# NRF_Transciever.net
KiCad netlist of a schematic drawn in Altium Designer
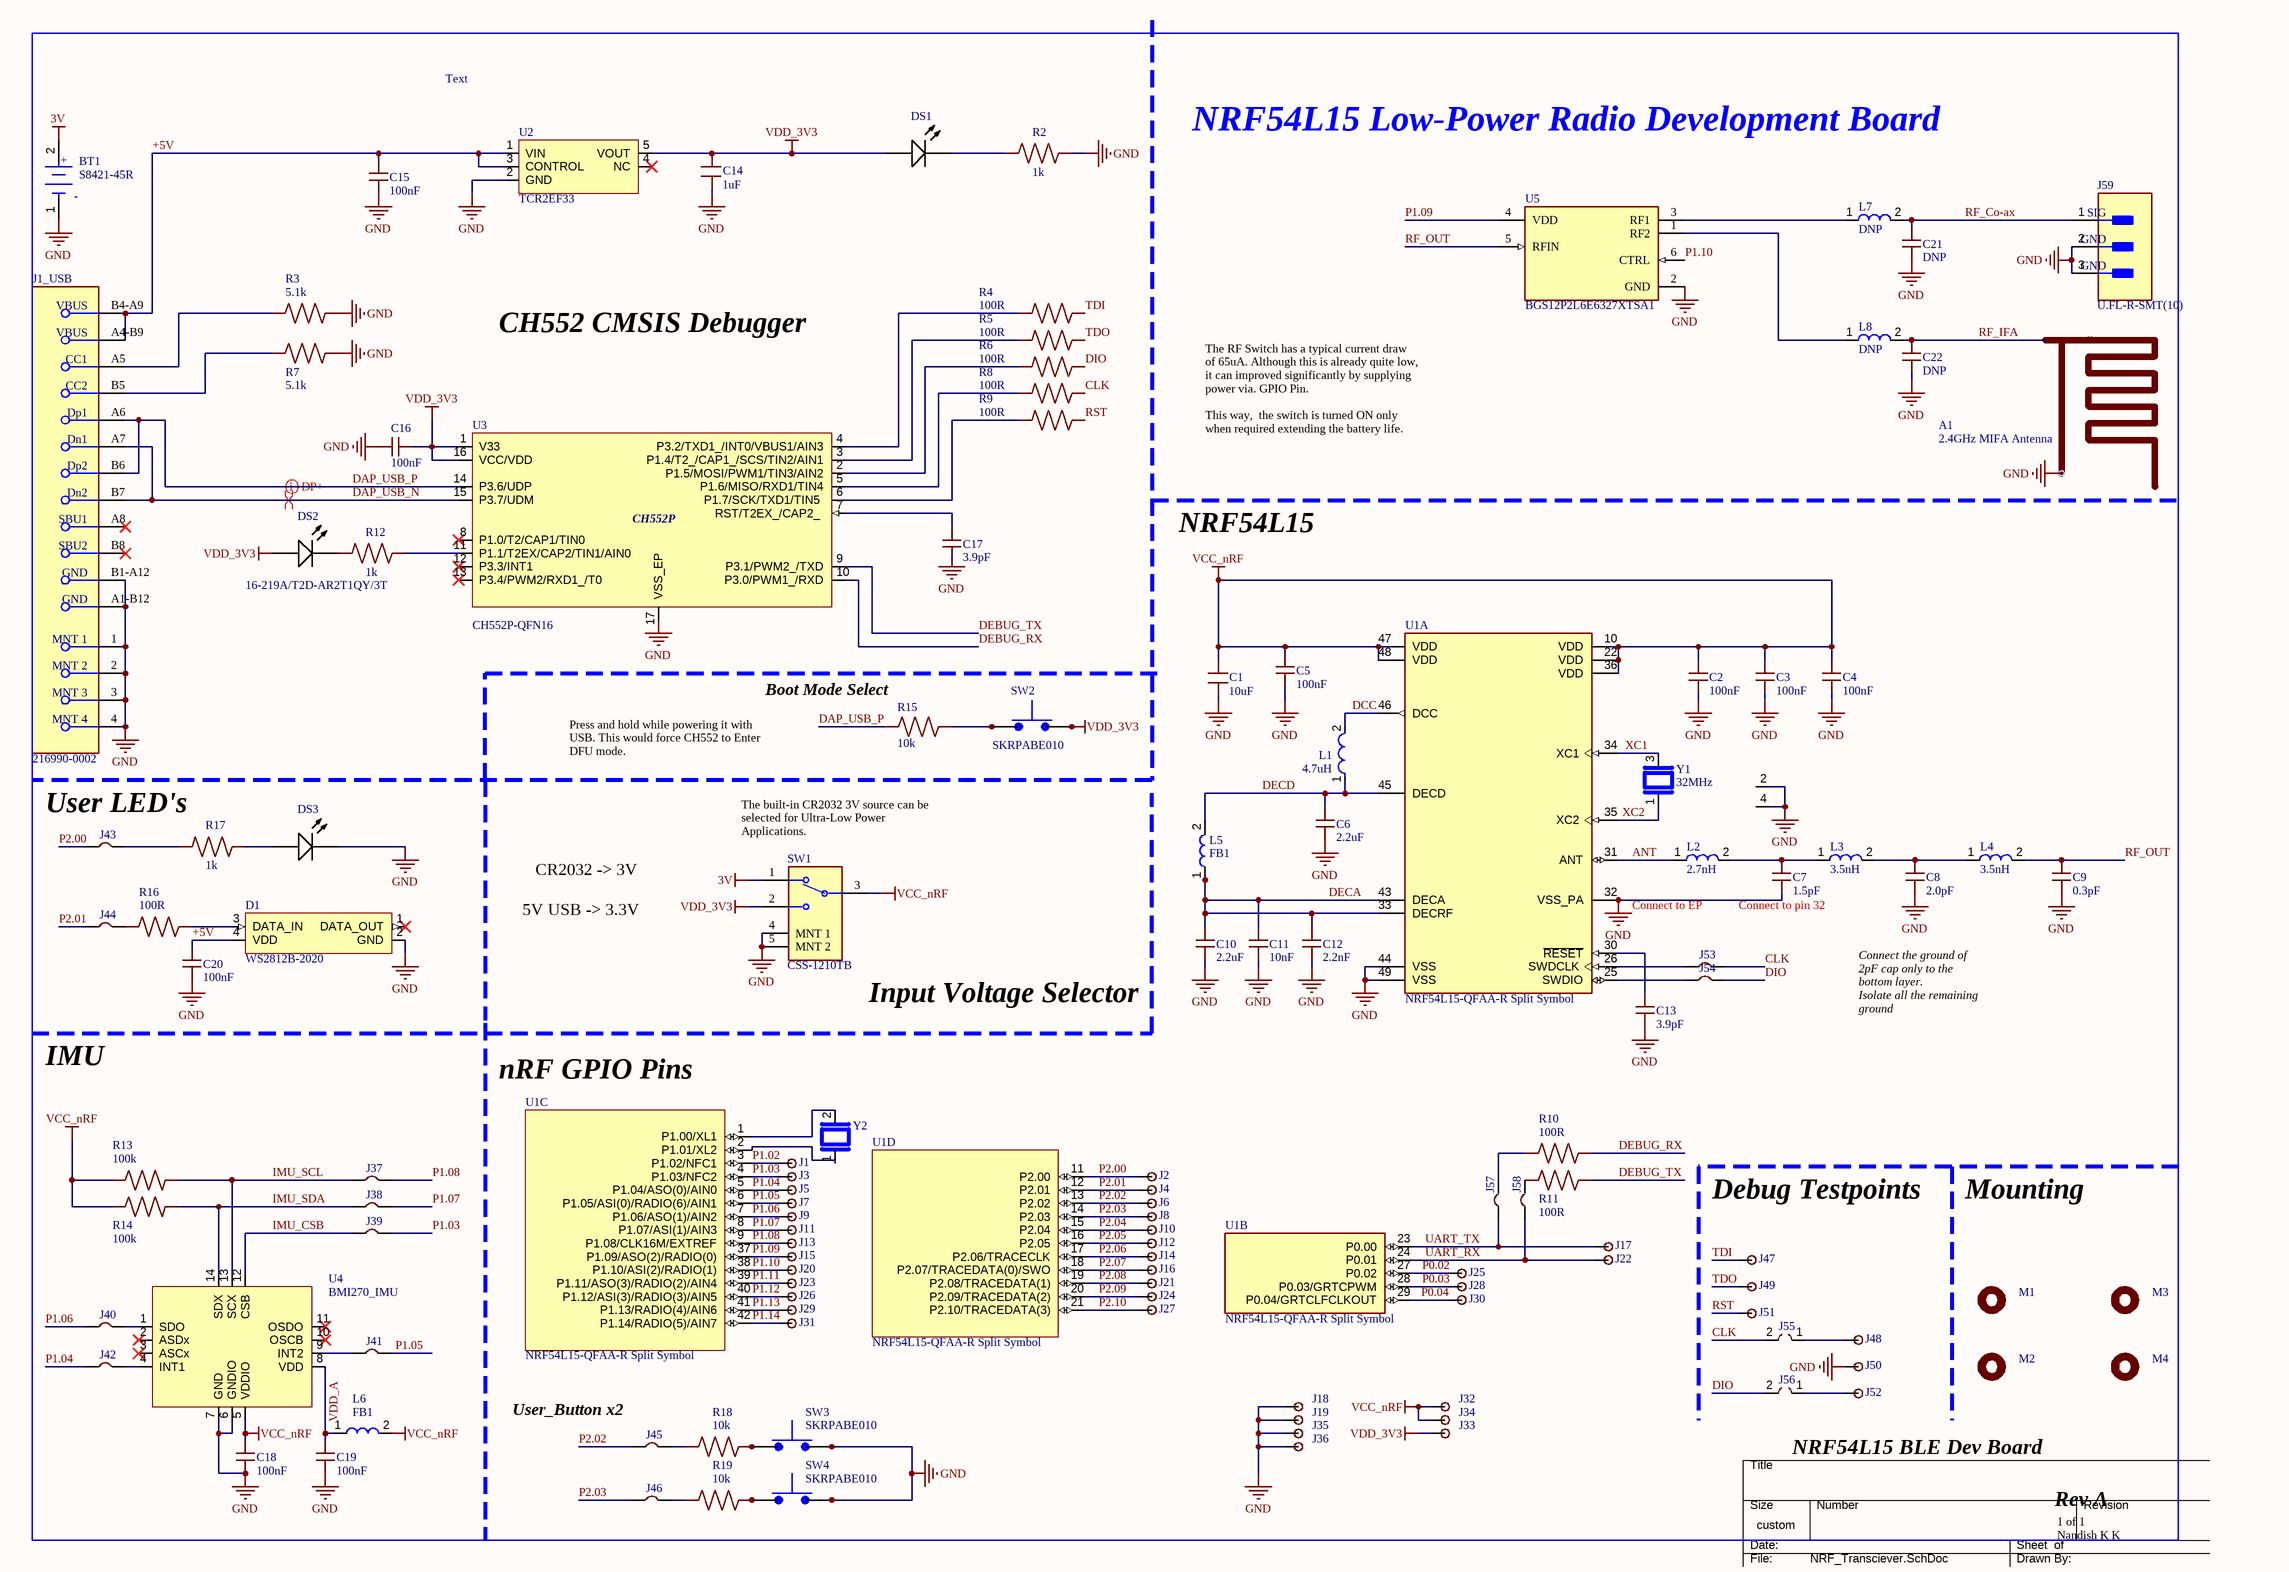
[diagram p0: NRF_Transciever.SchDoc]

(export (version "E")
  (design (tool "Eeschema 10.0.6"))
  (components
    (comp (ref "A1")
      (value "2.4GHz MIFA Antenna")
      (footprint "2.4GHz MIFA")
      (description "2.4GHz Meandered Inverted F Antenna from Cypress appnote AN91445")
      (libsource (lib "Generic_Schematic_Library") (part "2.4GHz MIFA"))
    )
    (comp (ref "BT1")
      (value "S8421-45R")
      (footprint "FP-S8421-45R-MFG")
      (description "BATTERY HOLDER COIN 20MM SMD")
      (libsource (lib "Altium Content Vault") (part "60d3b5b901a8747834971d0eb8cf3fd"))
    )
    (comp (ref "C1")
      (value "10uF")
      (footprint "0402_SMD_CAPACITOR")
      (description "Capacitor SMD 0402 Generic")
      (libsource (lib "Generic_Schematic_Library") (part "CAP_0402"))
    )
    (comp (ref "C2")
      (value "100nF")
      (footprint "0201 SMD Capacitor")
      (description "Capacitor SMD 0201 Generic")
      (libsource (lib "Generic_Schematic_Library") (part "CAP_0201"))
    )
    (comp (ref "C3")
      (value "100nF")
      (footprint "0201 SMD Capacitor")
      (description "Capacitor SMD 0201 Generic")
      (libsource (lib "Generic_Schematic_Library") (part "CAP_0201"))
    )
    (comp (ref "C4")
      (value "100nF")
      (footprint "0201 SMD Capacitor")
      (description "Capacitor SMD 0201 Generic")
      (libsource (lib "Generic_Schematic_Library") (part "CAP_0201"))
    )
    (comp (ref "C5")
      (value "100nF")
      (footprint "0201 SMD Capacitor")
      (description "Capacitor SMD 0201 Generic")
      (libsource (lib "Generic_Schematic_Library") (part "CAP_0201"))
    )
    (comp (ref "C6")
      (value "2.2uF")
      (footprint "0201 SMD Capacitor")
      (description "Capacitor SMD 0201 Generic")
      (libsource (lib "Generic_Schematic_Library") (part "CAP_0201"))
    )
    (comp (ref "C7")
      (value "1.5pF")
      (footprint "0201 SMD Capacitor")
      (description "Capacitor SMD 0201 Generic")
      (libsource (lib "Generic_Schematic_Library") (part "CAP_0201"))
    )
    (comp (ref "C8")
      (value "2.0pF")
      (footprint "0201 SMD Capacitor")
      (description "Capacitor SMD 0201 Generic")
      (libsource (lib "Generic_Schematic_Library") (part "CAP_0201"))
    )
    (comp (ref "C9")
      (value "0.3pF")
      (footprint "0201 SMD Capacitor")
      (description "Capacitor SMD 0201 Generic")
      (libsource (lib "Generic_Schematic_Library") (part "CAP_0201"))
    )
    (comp (ref "C10")
      (value "2.2uF")
      (footprint "0201 SMD Capacitor")
      (description "Capacitor SMD 0201 Generic")
      (libsource (lib "Generic_Schematic_Library") (part "CAP_0201"))
    )
    (comp (ref "C11")
      (value "10nF")
      (footprint "0201 SMD Capacitor")
      (description "Capacitor SMD 0201 Generic")
      (libsource (lib "Generic_Schematic_Library") (part "CAP_0201"))
    )
    (comp (ref "C12")
      (value "2.2nF")
      (footprint "0201 SMD Capacitor")
      (description "Capacitor SMD 0201 Generic")
      (libsource (lib "Generic_Schematic_Library") (part "CAP_0201"))
    )
    (comp (ref "C13")
      (value "3.9pF")
      (footprint "0201 SMD Capacitor")
      (description "Capacitor SMD 0201 Generic")
      (libsource (lib "Generic_Schematic_Library") (part "CAP_0201"))
    )
    (comp (ref "C14")
      (value "1uF")
      (footprint "0402_SMD_CAPACITOR")
      (description "Capacitor SMD 0402 Generic")
      (libsource (lib "Generic_Schematic_Library") (part "CAP_0402"))
    )
    (comp (ref "C15")
      (value "100nF")
      (footprint "0201 SMD Capacitor")
      (description "Capacitor SMD 0201 Generic")
      (libsource (lib "Generic_Schematic_Library") (part "CAP_0201"))
    )
    (comp (ref "C16")
      (value "100nF")
      (footprint "0201 SMD Capacitor")
      (description "Capacitor SMD 0201 Generic")
      (libsource (lib "Generic_Schematic_Library") (part "CAP_0201"))
    )
    (comp (ref "C17")
      (value "3.9pF")
      (footprint "0201 SMD Capacitor")
      (description "Capacitor SMD 0201 Generic")
      (libsource (lib "Generic_Schematic_Library") (part "CAP_0201"))
    )
    (comp (ref "C18")
      (value "100nF")
      (footprint "0201 SMD Capacitor")
      (description "Capacitor SMD 0201 Generic")
      (libsource (lib "Generic_Schematic_Library") (part "CAP_0201"))
    )
    (comp (ref "C19")
      (value "100nF")
      (footprint "0201 SMD Capacitor")
      (description "Capacitor SMD 0201 Generic")
      (libsource (lib "Generic_Schematic_Library") (part "CAP_0201"))
    )
    (comp (ref "C20")
      (value "100nF")
      (footprint "0201 SMD Capacitor")
      (description "Capacitor SMD 0201 Generic")
      (libsource (lib "Generic_Schematic_Library") (part "CAP_0201"))
    )
    (comp (ref "C21")
      (value "DNP")
      (footprint "0201 SMD Capacitor")
      (description "Capacitor SMD 0201 Generic")
      (libsource (lib "Generic_Schematic_Library") (part "CAP_0201"))
    )
    (comp (ref "C22")
      (value "DNP")
      (footprint "0201 SMD Capacitor")
      (description "Capacitor SMD 0201 Generic")
      (libsource (lib "Generic_Schematic_Library") (part "CAP_0201"))
    )
    (comp (ref "D1")
      (value "WS2812B-2020")
      (footprint "ws2812b-2020")
      (description "RGB LED (Built-in IC) 2x2mm SMD")
      (libsource (lib "Generic_Schematic_Library") (part "WS2812B-2020"))
    )
    (comp (ref "DS1")
      (value "16-219A/T2D-AR2T1QY/3T")
      (footprint "EVRL-0402-2_V")
      (description "Chip LED, White, 5 V, 10 mA, 30 mW, -40 to 85 degC, 2-Pin SMD (0402), RoHS, Tape and Reel")
      (fields (field (name "POWER") "30mW") (field (name "MANUFACTURER") "Everlight Electronics"))
      (libsource (lib "nandish kk") (part "LED-WHITE-AK-2"))
    )
    (comp (ref "DS2")
      (value "16-219A/T2D-AR2T1QY/3T")
      (footprint "EVRL-0402-2_V")
      (description "Chip LED, White, 5 V, 10 mA, 30 mW, -40 to 85 degC, 2-Pin SMD (0402), RoHS, Tape and Reel")
      (fields (field (name "POWER") "30mW") (field (name "MANUFACTURER") "Everlight Electronics"))
      (libsource (lib "nandish kk") (part "LED-WHITE-AK-2"))
    )
    (comp (ref "DS3")
      (value "16-219A/T2D-AR2T1QY/3T")
      (footprint "EVRL-0402-2_V")
      (description "Chip LED, White, 5 V, 10 mA, 30 mW, -40 to 85 degC, 2-Pin SMD (0402), RoHS, Tape and Reel")
      (fields (field (name "POWER") "30mW") (field (name "MANUFACTURER") "Everlight Electronics"))
      (libsource (lib "nandish kk") (part "LED-WHITE-AK-2"))
    )
    (comp (ref "J1")
      (value "Single_Header_2.54mm")
      (footprint "Single_Header_2.54mm")
      (libsource (lib "Generic_Schematic_Library") (part "Single_Header_2.54mm"))
    )
    (comp (ref "J1_USB")
      (value "216990-0002")
      (footprint "FP-216990-0002-MFG")
      (description "CONN RCP USB2.0 TYP C 24P SMD RA")
      (libsource (lib "Altium Content Vault") (part "7e081d3bdd84dd7df1daf8a7a06d5b3"))
    )
    (comp (ref "J2")
      (value "Single_Header_2.54mm")
      (footprint "Single_Header_2.54mm")
      (libsource (lib "Generic_Schematic_Library") (part "Single_Header_2.54mm"))
    )
    (comp (ref "J3")
      (value "Single_Header_2.54mm")
      (footprint "Single_Header_2.54mm")
      (libsource (lib "Generic_Schematic_Library") (part "Single_Header_2.54mm"))
    )
    (comp (ref "J4")
      (value "Single_Header_2.54mm")
      (footprint "Single_Header_2.54mm")
      (libsource (lib "Generic_Schematic_Library") (part "Single_Header_2.54mm"))
    )
    (comp (ref "J5")
      (value "Single_Header_2.54mm")
      (footprint "Single_Header_2.54mm")
      (libsource (lib "Generic_Schematic_Library") (part "Single_Header_2.54mm"))
    )
    (comp (ref "J6")
      (value "Single_Header_2.54mm")
      (footprint "Single_Header_2.54mm")
      (libsource (lib "Generic_Schematic_Library") (part "Single_Header_2.54mm"))
    )
    (comp (ref "J7")
      (value "Single_Header_2.54mm")
      (footprint "Single_Header_2.54mm")
      (libsource (lib "Generic_Schematic_Library") (part "Single_Header_2.54mm"))
    )
    (comp (ref "J8")
      (value "Single_Header_2.54mm")
      (footprint "Single_Header_2.54mm")
      (libsource (lib "Generic_Schematic_Library") (part "Single_Header_2.54mm"))
    )
    (comp (ref "J9")
      (value "Single_Header_2.54mm")
      (footprint "Single_Header_2.54mm")
      (libsource (lib "Generic_Schematic_Library") (part "Single_Header_2.54mm"))
    )
    (comp (ref "J10")
      (value "Single_Header_2.54mm")
      (footprint "Single_Header_2.54mm")
      (libsource (lib "Generic_Schematic_Library") (part "Single_Header_2.54mm"))
    )
    (comp (ref "J11")
      (value "Single_Header_2.54mm")
      (footprint "Single_Header_2.54mm")
      (libsource (lib "Generic_Schematic_Library") (part "Single_Header_2.54mm"))
    )
    (comp (ref "J12")
      (value "Single_Header_2.54mm")
      (footprint "Single_Header_2.54mm")
      (libsource (lib "Generic_Schematic_Library") (part "Single_Header_2.54mm"))
    )
    (comp (ref "J13")
      (value "Single_Header_2.54mm")
      (footprint "Single_Header_2.54mm")
      (libsource (lib "Generic_Schematic_Library") (part "Single_Header_2.54mm"))
    )
    (comp (ref "J14")
      (value "Single_Header_2.54mm")
      (footprint "Single_Header_2.54mm")
      (libsource (lib "Generic_Schematic_Library") (part "Single_Header_2.54mm"))
    )
    (comp (ref "J15")
      (value "Single_Header_2.54mm")
      (footprint "Single_Header_2.54mm")
      (libsource (lib "Generic_Schematic_Library") (part "Single_Header_2.54mm"))
    )
    (comp (ref "J16")
      (value "Single_Header_2.54mm")
      (footprint "Single_Header_2.54mm")
      (libsource (lib "Generic_Schematic_Library") (part "Single_Header_2.54mm"))
    )
    (comp (ref "J17")
      (value "Single_Header_2.54mm")
      (footprint "Single_Header_2.54mm")
      (libsource (lib "Generic_Schematic_Library") (part "Single_Header_2.54mm"))
    )
    (comp (ref "J18")
      (value "Single_Header_2.54mm")
      (footprint "Single_Header_2.54mm")
      (libsource (lib "Generic_Schematic_Library") (part "Single_Header_2.54mm"))
    )
    (comp (ref "J19")
      (value "Single_Header_2.54mm")
      (footprint "Single_Header_2.54mm")
      (libsource (lib "Generic_Schematic_Library") (part "Single_Header_2.54mm"))
    )
    (comp (ref "J20")
      (value "Single_Header_2.54mm")
      (footprint "Single_Header_2.54mm")
      (libsource (lib "Generic_Schematic_Library") (part "Single_Header_2.54mm"))
    )
    (comp (ref "J21")
      (value "Single_Header_2.54mm")
      (footprint "Single_Header_2.54mm")
      (libsource (lib "Generic_Schematic_Library") (part "Single_Header_2.54mm"))
    )
    (comp (ref "J22")
      (value "Single_Header_2.54mm")
      (footprint "Single_Header_2.54mm")
      (libsource (lib "Generic_Schematic_Library") (part "Single_Header_2.54mm"))
    )
    (comp (ref "J23")
      (value "Single_Header_2.54mm")
      (footprint "Single_Header_2.54mm")
      (libsource (lib "Generic_Schematic_Library") (part "Single_Header_2.54mm"))
    )
    (comp (ref "J24")
      (value "Single_Header_2.54mm")
      (footprint "Single_Header_2.54mm")
      (libsource (lib "Generic_Schematic_Library") (part "Single_Header_2.54mm"))
    )
    (comp (ref "J25")
      (value "Single_Header_2.54mm")
      (footprint "Single_Header_2.54mm")
      (libsource (lib "Generic_Schematic_Library") (part "Single_Header_2.54mm"))
    )
    (comp (ref "J26")
      (value "Single_Header_2.54mm")
      (footprint "Single_Header_2.54mm")
      (libsource (lib "Generic_Schematic_Library") (part "Single_Header_2.54mm"))
    )
    (comp (ref "J27")
      (value "Single_Header_2.54mm")
      (footprint "Single_Header_2.54mm")
      (libsource (lib "Generic_Schematic_Library") (part "Single_Header_2.54mm"))
    )
    (comp (ref "J28")
      (value "Single_Header_2.54mm")
      (footprint "Single_Header_2.54mm")
      (libsource (lib "Generic_Schematic_Library") (part "Single_Header_2.54mm"))
    )
    (comp (ref "J29")
      (value "Single_Header_2.54mm")
      (footprint "Single_Header_2.54mm")
      (libsource (lib "Generic_Schematic_Library") (part "Single_Header_2.54mm"))
    )
    (comp (ref "J30")
      (value "Single_Header_2.54mm")
      (footprint "Single_Header_2.54mm")
      (libsource (lib "Generic_Schematic_Library") (part "Single_Header_2.54mm"))
    )
    (comp (ref "J31")
      (value "Single_Header_2.54mm")
      (footprint "Single_Header_2.54mm")
      (libsource (lib "Generic_Schematic_Library") (part "Single_Header_2.54mm"))
    )
    (comp (ref "J32")
      (value "Single_Header_2.54mm")
      (footprint "Single_Header_2.54mm")
      (libsource (lib "Generic_Schematic_Library") (part "Single_Header_2.54mm"))
    )
    (comp (ref "J33")
      (value "Single_Header_2.54mm")
      (footprint "Single_Header_2.54mm")
      (libsource (lib "Generic_Schematic_Library") (part "Single_Header_2.54mm"))
    )
    (comp (ref "J34")
      (value "Single_Header_2.54mm")
      (footprint "Single_Header_2.54mm")
      (libsource (lib "Generic_Schematic_Library") (part "Single_Header_2.54mm"))
    )
    (comp (ref "J35")
      (value "Single_Header_2.54mm")
      (footprint "Single_Header_2.54mm")
      (libsource (lib "Generic_Schematic_Library") (part "Single_Header_2.54mm"))
    )
    (comp (ref "J36")
      (value "Single_Header_2.54mm")
      (footprint "Single_Header_2.54mm")
      (libsource (lib "Generic_Schematic_Library") (part "Single_Header_2.54mm"))
    )
    (comp (ref "J37")
      (value "Shorted_Solder_Bridge")
      (footprint "SHORTED_SOLDER_BRIDGE")
      (libsource (lib "Generic_Schematic_Library") (part "Shorted_Solder_Bridge"))
    )
    (comp (ref "J38")
      (value "Shorted_Solder_Bridge")
      (footprint "SHORTED_SOLDER_BRIDGE")
      (libsource (lib "Generic_Schematic_Library") (part "Shorted_Solder_Bridge"))
    )
    (comp (ref "J39")
      (value "Shorted_Solder_Bridge")
      (footprint "SHORTED_SOLDER_BRIDGE")
      (libsource (lib "Generic_Schematic_Library") (part "Shorted_Solder_Bridge"))
    )
    (comp (ref "J40")
      (value "Shorted_Solder_Bridge")
      (footprint "SHORTED_SOLDER_BRIDGE")
      (libsource (lib "Generic_Schematic_Library") (part "Shorted_Solder_Bridge"))
    )
    (comp (ref "J41")
      (value "Shorted_Solder_Bridge")
      (footprint "SHORTED_SOLDER_BRIDGE")
      (libsource (lib "Generic_Schematic_Library") (part "Shorted_Solder_Bridge"))
    )
    (comp (ref "J42")
      (value "Shorted_Solder_Bridge")
      (footprint "SHORTED_SOLDER_BRIDGE")
      (libsource (lib "Generic_Schematic_Library") (part "Shorted_Solder_Bridge"))
    )
    (comp (ref "J43")
      (value "Shorted_Solder_Bridge")
      (footprint "SHORTED_SOLDER_BRIDGE")
      (libsource (lib "Generic_Schematic_Library") (part "Shorted_Solder_Bridge"))
    )
    (comp (ref "J44")
      (value "Shorted_Solder_Bridge")
      (footprint "SHORTED_SOLDER_BRIDGE")
      (libsource (lib "Generic_Schematic_Library") (part "Shorted_Solder_Bridge"))
    )
    (comp (ref "J45")
      (value "Shorted_Solder_Bridge")
      (footprint "SHORTED_SOLDER_BRIDGE")
      (libsource (lib "Generic_Schematic_Library") (part "Shorted_Solder_Bridge"))
    )
    (comp (ref "J46")
      (value "Shorted_Solder_Bridge")
      (footprint "SHORTED_SOLDER_BRIDGE")
      (libsource (lib "Generic_Schematic_Library") (part "Shorted_Solder_Bridge"))
    )
    (comp (ref "J47")
      (value "Single_Header_2.54mm")
      (footprint "Single_Header_2.54mm")
      (libsource (lib "Generic_Schematic_Library") (part "Single_Header_2.54mm"))
    )
    (comp (ref "J48")
      (value "Single_Header_2.54mm")
      (footprint "Single_Header_2.54mm")
      (libsource (lib "Generic_Schematic_Library") (part "Single_Header_2.54mm"))
    )
    (comp (ref "J49")
      (value "Single_Header_2.54mm")
      (footprint "Single_Header_2.54mm")
      (libsource (lib "Generic_Schematic_Library") (part "Single_Header_2.54mm"))
    )
    (comp (ref "J50")
      (value "Single_Header_2.54mm")
      (footprint "Single_Header_2.54mm")
      (libsource (lib "Generic_Schematic_Library") (part "Single_Header_2.54mm"))
    )
    (comp (ref "J51")
      (value "Single_Header_2.54mm")
      (footprint "Single_Header_2.54mm")
      (libsource (lib "Generic_Schematic_Library") (part "Single_Header_2.54mm"))
    )
    (comp (ref "J52")
      (value "Single_Header_2.54mm")
      (footprint "Single_Header_2.54mm")
      (libsource (lib "Generic_Schematic_Library") (part "Single_Header_2.54mm"))
    )
    (comp (ref "J53")
      (value "Shorted_Solder_Bridge")
      (footprint "SHORTED_SOLDER_BRIDGE")
      (libsource (lib "Generic_Schematic_Library") (part "Shorted_Solder_Bridge"))
    )
    (comp (ref "J54")
      (value "Shorted_Solder_Bridge")
      (footprint "SHORTED_SOLDER_BRIDGE")
      (libsource (lib "Generic_Schematic_Library") (part "Shorted_Solder_Bridge"))
    )
    (comp (ref "J55")
      (value "Open_Solder_Bridge")
      (footprint "Open_Solder_bridge")
      (libsource (lib "Generic_Schematic_Library") (part "Open_Solder_Bridge"))
    )
    (comp (ref "J56")
      (value "Open_Solder_Bridge")
      (footprint "Open_Solder_bridge")
      (libsource (lib "Generic_Schematic_Library") (part "Open_Solder_Bridge"))
    )
    (comp (ref "J57")
      (value "Shorted_Solder_Bridge")
      (footprint "SHORTED_SOLDER_BRIDGE")
      (libsource (lib "Generic_Schematic_Library") (part "Shorted_Solder_Bridge"))
    )
    (comp (ref "J58")
      (value "Shorted_Solder_Bridge")
      (footprint "SHORTED_SOLDER_BRIDGE")
      (libsource (lib "Generic_Schematic_Library") (part "Shorted_Solder_Bridge"))
    )
    (comp (ref "J59")
      (value "U.FL-R-SMT(10)")
      (footprint "FP-U_FL-R-SMT_10-MFG")
      (description "CONN U.FL RCPT STR 50 OHM SMD")
      (libsource (lib "Altium Content Vault") (part "eef6fde44c591823e8076210edfe12f"))
    )
    (comp (ref "L1")
      (value "4.7uH")
      (footprint "FP-MLZ1608-IPC_A")
      (description "Shielded Multilayer Inductor 4.7uH ±20% 350mA 650mΩ SMD 0603")
      (fields (field (name "TOLERANCE") "20%"))
      (libsource (lib "Altium Content Vault") (part "725321dda6339637d4d059423bc1c3c"))
    )
    (comp (ref "L2")
      (value "2.7nH")
      (footprint "0201_SMD_INDUCTOR")
      (description "Inductor SMD 0201 Generic")
      (libsource (lib "Generic_Schematic_Library") (part "INDUCTOR_0201"))
    )
    (comp (ref "L3")
      (value "3.5nH")
      (footprint "0201_SMD_INDUCTOR")
      (description "Inductor SMD 0201 Generic")
      (libsource (lib "Generic_Schematic_Library") (part "INDUCTOR_0201"))
    )
    (comp (ref "L4")
      (value "3.5nH")
      (footprint "0201_SMD_INDUCTOR")
      (description "Inductor SMD 0201 Generic")
      (libsource (lib "Generic_Schematic_Library") (part "INDUCTOR_0201"))
    )
    (comp (ref "L5")
      (value "FB1")
      (footprint "0201_SMD_INDUCTOR")
      (description "Inductor SMD 0201 Generic")
      (libsource (lib "Generic_Schematic_Library") (part "INDUCTOR_0201"))
    )
    (comp (ref "L6")
      (value "FB1")
      (footprint "0201_SMD_INDUCTOR")
      (description "Inductor SMD 0201 Generic")
      (libsource (lib "Generic_Schematic_Library") (part "INDUCTOR_0201"))
    )
    (comp (ref "L7")
      (value "DNP")
      (footprint "0201_SMD_INDUCTOR")
      (description "Inductor SMD 0201 Generic")
      (libsource (lib "Generic_Schematic_Library") (part "INDUCTOR_0201"))
    )
    (comp (ref "L8")
      (value "DNP")
      (footprint "0201_SMD_INDUCTOR")
      (description "Inductor SMD 0201 Generic")
      (libsource (lib "Generic_Schematic_Library") (part "INDUCTOR_0201"))
    )
    (comp (ref "M1")
      (value "M2_Mounting_Hole")
      (footprint "M2 Mounting hole")
      (description "M2 Screw mounting hole.\r\nActual dia. 2.2 mm")
      (libsource (lib "Generic_Schematic_Library") (part "M2_Mounting_Hole"))
    )
    (comp (ref "M2")
      (value "M2_Mounting_Hole")
      (footprint "M2 Mounting hole")
      (description "M2 Screw mounting hole.\r\nActual dia. 2.2 mm")
      (libsource (lib "Generic_Schematic_Library") (part "M2_Mounting_Hole"))
    )
    (comp (ref "M3")
      (value "M2_Mounting_Hole")
      (footprint "M2 Mounting hole")
      (description "M2 Screw mounting hole.\r\nActual dia. 2.2 mm")
      (libsource (lib "Generic_Schematic_Library") (part "M2_Mounting_Hole"))
    )
    (comp (ref "M4")
      (value "M2_Mounting_Hole")
      (footprint "M2 Mounting hole")
      (description "M2 Screw mounting hole.\r\nActual dia. 2.2 mm")
      (libsource (lib "Generic_Schematic_Library") (part "M2_Mounting_Hole"))
    )
    (comp (ref "R2")
      (value "1k")
      (footprint "RES_0402_Generic")
      (description "Resistor SMD 0402 Generic")
      (libsource (lib "Generic_Schematic_Library") (part "RES_0402"))
    )
    (comp (ref "R3")
      (value "5.1k")
      (footprint "RES_0402_Generic")
      (description "Resistor SMD 0402 Generic")
      (libsource (lib "Generic_Schematic_Library") (part "RES_0402"))
    )
    (comp (ref "R4")
      (value "100R")
      (footprint "RES_0402_Generic")
      (description "Resistor SMD 0402 Generic")
      (libsource (lib "Generic_Schematic_Library") (part "RES_0402"))
    )
    (comp (ref "R5")
      (value "100R")
      (footprint "RES_0402_Generic")
      (description "Resistor SMD 0402 Generic")
      (libsource (lib "Generic_Schematic_Library") (part "RES_0402"))
    )
    (comp (ref "R6")
      (value "100R")
      (footprint "RES_0402_Generic")
      (description "Resistor SMD 0402 Generic")
      (libsource (lib "Generic_Schematic_Library") (part "RES_0402"))
    )
    (comp (ref "R7")
      (value "5.1k")
      (footprint "RES_0402_Generic")
      (description "Resistor SMD 0402 Generic")
      (libsource (lib "Generic_Schematic_Library") (part "RES_0402"))
    )
    (comp (ref "R8")
      (value "100R")
      (footprint "RES_0402_Generic")
      (description "Resistor SMD 0402 Generic")
      (libsource (lib "Generic_Schematic_Library") (part "RES_0402"))
    )
    (comp (ref "R9")
      (value "100R")
      (footprint "RES_0402_Generic")
      (description "Resistor SMD 0402 Generic")
      (libsource (lib "Generic_Schematic_Library") (part "RES_0402"))
    )
    (comp (ref "R10")
      (value "100R")
      (footprint "RES_0402_Generic")
      (description "Resistor SMD 0402 Generic")
      (libsource (lib "Generic_Schematic_Library") (part "RES_0402"))
    )
    (comp (ref "R11")
      (value "100R")
      (footprint "RES_0402_Generic")
      (description "Resistor SMD 0402 Generic")
      (libsource (lib "Generic_Schematic_Library") (part "RES_0402"))
    )
    (comp (ref "R12")
      (value "1k")
      (footprint "RES_0402_Generic")
      (description "Resistor SMD 0402 Generic")
      (libsource (lib "Generic_Schematic_Library") (part "RES_0402"))
    )
    (comp (ref "R13")
      (value "100k")
      (footprint "RES_0402_Generic")
      (description "Resistor SMD 0402 Generic")
      (libsource (lib "Generic_Schematic_Library") (part "RES_0402"))
    )
    (comp (ref "R14")
      (value "100k")
      (footprint "RES_0402_Generic")
      (description "Resistor SMD 0402 Generic")
      (libsource (lib "Generic_Schematic_Library") (part "RES_0402"))
    )
    (comp (ref "R15")
      (value "10k")
      (footprint "RES_0402_Generic")
      (description "Resistor SMD 0402 Generic")
      (libsource (lib "Generic_Schematic_Library") (part "RES_0402"))
    )
    (comp (ref "R16")
      (value "100R")
      (footprint "RES_0402_Generic")
      (description "Resistor SMD 0402 Generic")
      (libsource (lib "Generic_Schematic_Library") (part "RES_0402"))
    )
    (comp (ref "R17")
      (value "1k")
      (footprint "RES_0402_Generic")
      (description "Resistor SMD 0402 Generic")
      (libsource (lib "Generic_Schematic_Library") (part "RES_0402"))
    )
    (comp (ref "R18")
      (value "10k")
      (footprint "RES_0402_Generic")
      (description "Resistor SMD 0402 Generic")
      (libsource (lib "Generic_Schematic_Library") (part "RES_0402"))
    )
    (comp (ref "R19")
      (value "10k")
      (footprint "RES_0402_Generic")
      (description "Resistor SMD 0402 Generic")
      (libsource (lib "Generic_Schematic_Library") (part "RES_0402"))
    )
    (comp (ref "SW1")
      (value "CSS-1210TB")
      (footprint "FP-CSS-1210TB-MFG")
      (description "SWITCH SLIDE SPDT 100MA 12V")
      (libsource (lib "Altium Content Vault") (part "235c6d1c3a5894744d06c60f0199c3d"))
    )
    (comp (ref "SW2")
      (value "SKRPABE010")
      (footprint "SW_SKRPABE010")
      (description "Switch Tactile N.O. SPST Button J-Bend 0.05A 16VDC 1.57N SMD Automotive T/R")
      (fields (field (name "MF") "ALPS"))
      (libsource (lib "nandish kk") (part "SKRPABE010"))
    )
    (comp (ref "SW3")
      (value "SKRPABE010")
      (footprint "SW_SKRPABE010")
      (description "Switch Tactile N.O. SPST Button J-Bend 0.05A 16VDC 1.57N SMD Automotive T/R")
      (fields (field (name "MF") "ALPS"))
      (libsource (lib "nandish kk") (part "SKRPABE010"))
    )
    (comp (ref "SW4")
      (value "SKRPABE010")
      (footprint "SW_SKRPABE010")
      (description "Switch Tactile N.O. SPST Button J-Bend 0.05A 16VDC 1.57N SMD Automotive T/R")
      (fields (field (name "MF") "ALPS"))
      (libsource (lib "nandish kk") (part "SKRPABE010"))
    )
    (comp (ref "U1")
      (value "NRF54L15-QFAA-R Split Symbol")
      (footprint "NRF54L15_LQFN_48")
      (fields
        (field (name "MP") "NRF54L15-QFAA-R")
        (field (name "MF") "{'manufacturer': u'Nordic Semiconductor ASA'}")
      )
      (libsource (lib "Generic_Schematic_Library") (part "NRF54L15-QFAA-R"))
    )
    (comp (ref "U2")
      (value "TCR2EF33")
      (footprint "TCR2EF33-SOT-23-5")
      (libsource (lib "Generic_Schematic_Library") (part "TCR2EF33"))
    )
    (comp (ref "U3")
      (value "CH552P-QFN16")
      (footprint "CH552-QFN16_3x3")
      (libsource (lib "Generic_Schematic_Library") (part "CH552P-QFN16"))
    )
    (comp (ref "U4")
      (value "BMI270_IMU")
      (footprint "BMI_270_PQFN50P300X250X70-14L")
      (description "6-axis IMU")
      (libsource (lib "Generic_Schematic_Library") (part "BMI270_IMU"))
    )
    (comp (ref "U5")
      (value "BGS12P2L6E6327XTSA1")
      (footprint "FP-PG-TSLP-6-MFG")
      (description "CMOS SWITCH")
      (libsource (lib "Altium Content Vault") (part "6afaab1f0fd49b7196d94c032830f09"))
    )
    (comp (ref "Y1")
      (value "32MHz")
      (footprint "OSC_XRCGB32M000F2P01R0")
      (description "32MHz Â±20ppm Crystal 8pF 100 Ohms 4-SMD, No Lead")
      (fields (field (name "MP") "XRCGB32M000F2P01R0") (field (name "MF") "Murata Electronics"))
      (libsource (lib "nandish kk") (part "XRCGB32M000F2P01R0"))
    )
    (comp (ref "Y2")
      (value "CM8V-T1A-32.768KHZ-9PF-20PPM-TA-QC")
      (footprint "XTAL_CM8V-T1A-32.768KHZ-9PF-20PPM-TA-QC")
      (description "Tuning Fork Crystal 32.768kHz in 1.2 x 2.0mm package")
      (fields (field (name "MF") "Micro Crystal"))
      (libsource (lib "nandish kk") (part "CM8V-T1A-32.768KHZ-9PF-20PPM-TA-QC"))
    )
  )
  (nets
    (net (code "1") (name "/+5V") (class "Default")
      (node (ref "C15") (pin "2") (pintype "passive"))
      (node (ref "C20") (pin "2") (pintype "passive"))
      (node (ref "D1") (pin "4") (pinfunction "VDD_4") (pintype "power_in"))
      (node (ref "J1_USB") (pin "A4-B9") (pinfunction "VBUS_A4-B9") (pintype "passive"))
      (node (ref "J1_USB") (pin "B4-A9") (pinfunction "VBUS_B4-A9") (pintype "passive"))
      (node (ref "U2") (pin "1") (pinfunction "VIN_1") (pintype "power_in"))
      (node (ref "U2") (pin "3") (pinfunction "CONTROL_3") (pintype "power_in"))
    )
    (net (code "2") (name "/ANT") (class "Default")
      (node (ref "L2") (pin "1") (pinfunction "1_1") (pintype "passive"))
      (node (ref "U1") (pin "31") (pinfunction "ANT_31") (pintype "bidirectional"))
    )
    (net (code "3") (name "/CLK") (class "Default")
      (node (ref "J53") (pin "2") (pinfunction "_2_2") (pintype "passive"))
      (node (ref "J55") (pin "2") (pinfunction "_2_2") (pintype "passive"))
      (node (ref "R8") (pin "2") (pintype "passive"))
    )
    (net (code "4") (name "/DAP_USB_N") (class "Default")
      (node (ref "J1_USB") (pin "A7") (pinfunction "Dn1_A7") (pintype "passive"))
      (node (ref "J1_USB") (pin "B7") (pinfunction "Dn2_B7") (pintype "passive"))
      (node (ref "U3") (pin "15") (pinfunction "P3.7/UDM_15") (pintype "bidirectional"))
    )
    (net (code "5") (name "/DAP_USB_P") (class "Default")
      (node (ref "J1_USB") (pin "A6") (pinfunction "Dp1_A6") (pintype "passive"))
      (node (ref "J1_USB") (pin "B6") (pinfunction "Dp2_B6") (pintype "passive"))
      (node (ref "R15") (pin "1") (pintype "passive"))
      (node (ref "U3") (pin "14") (pinfunction "P3.6/UDP_14") (pintype "bidirectional"))
    )
    (net (code "6") (name "/DCC") (class "Default")
      (node (ref "L1") (pin "2") (pinfunction "2_2") (pintype "passive"))
      (node (ref "U1") (pin "46") (pinfunction "DCC_46") (pintype "output"))
    )
    (net (code "7") (name "/DEBUG_RX") (class "Default")
      (node (ref "R10") (pin "1") (pintype "passive"))
      (node (ref "U3") (pin "10") (pinfunction "P3.0/PWM1_/RXD_10") (pintype "bidirectional"))
    )
    (net (code "8") (name "/DEBUG_TX") (class "Default")
      (node (ref "R11") (pin "2") (pintype "passive"))
      (node (ref "U3") (pin "9") (pinfunction "P3.1/PWM2_/TXD_9") (pintype "bidirectional"))
    )
    (net (code "9") (name "/DECA") (class "Default")
      (node (ref "C10") (pin "2") (pintype "passive"))
      (node (ref "C11") (pin "2") (pintype "passive"))
      (node (ref "C12") (pin "2") (pintype "passive"))
      (node (ref "L5") (pin "1") (pinfunction "1_1") (pintype "passive"))
      (node (ref "U1") (pin "33") (pinfunction "DECRF_33") (pintype "power_in"))
      (node (ref "U1") (pin "43") (pinfunction "DECA_43") (pintype "power_in"))
    )
    (net (code "10") (name "/DECD") (class "Default")
      (node (ref "C6") (pin "2") (pintype "passive"))
      (node (ref "L1") (pin "1") (pinfunction "1_1") (pintype "passive"))
      (node (ref "L5") (pin "2") (pinfunction "2_2") (pintype "passive"))
      (node (ref "U1") (pin "45") (pinfunction "DECD_45") (pintype "power_in"))
    )
    (net (code "11") (name "/DIO") (class "Default")
      (node (ref "J54") (pin "2") (pinfunction "_2_2") (pintype "passive"))
      (node (ref "J56") (pin "2") (pinfunction "_2_2") (pintype "passive"))
      (node (ref "R6") (pin "2") (pintype "passive"))
    )
    (net (code "12") (name "/IMU_CSB") (class "Default")
      (node (ref "J39") (pin "1") (pinfunction "_1_1") (pintype "passive"))
      (node (ref "U4") (pin "12") (pinfunction "CSB_12") (pintype "passive"))
    )
    (net (code "13") (name "/IMU_SCL") (class "Default")
      (node (ref "J37") (pin "1") (pinfunction "_1_1") (pintype "passive"))
      (node (ref "R13") (pin "1") (pintype "passive"))
      (node (ref "U4") (pin "13") (pinfunction "SCX_13") (pintype "passive"))
    )
    (net (code "14") (name "/IMU_SDA") (class "Default")
      (node (ref "J38") (pin "1") (pinfunction "_1_1") (pintype "passive"))
      (node (ref "R14") (pin "1") (pintype "passive"))
      (node (ref "U4") (pin "14") (pinfunction "SDX_14") (pintype "passive"))
    )
    (net (code "15") (name "/P0.02") (class "Default")
      (node (ref "J25") (pin "1") (pinfunction "1_1") (pintype "passive"))
      (node (ref "U1") (pin "27") (pinfunction "P0.02_27") (pintype "bidirectional"))
    )
    (net (code "16") (name "/P0.03") (class "Default")
      (node (ref "J28") (pin "1") (pinfunction "1_1") (pintype "passive"))
      (node (ref "U1") (pin "28") (pinfunction "P0.03/GRTCPWM_28") (pintype "bidirectional"))
    )
    (net (code "17") (name "/P0.04") (class "Default")
      (node (ref "J30") (pin "1") (pinfunction "1_1") (pintype "passive"))
      (node (ref "U1") (pin "29") (pinfunction "P0.04/GRTCLFCLKOUT_29") (pintype "bidirectional"))
    )
    (net (code "18") (name "/P1.02") (class "Default")
      (node (ref "J1") (pin "1") (pinfunction "1_1") (pintype "passive"))
      (node (ref "U1") (pin "3") (pinfunction "P1.02/NFC1_3") (pintype "bidirectional"))
    )
    (net (code "19") (name "/P1.03") (class "Default")
      (node (ref "J3") (pin "1") (pinfunction "1_1") (pintype "passive"))
      (node (ref "J39") (pin "2") (pinfunction "_2_2") (pintype "passive"))
      (node (ref "U1") (pin "4") (pinfunction "P1.03/NFC2_4") (pintype "bidirectional"))
    )
    (net (code "20") (name "/P1.04") (class "Default")
      (node (ref "J42") (pin "1") (pinfunction "_1_1") (pintype "passive"))
      (node (ref "J5") (pin "1") (pinfunction "1_1") (pintype "passive"))
      (node (ref "U1") (pin "5") (pinfunction "P1.04/ASO(0)/AIN0_5") (pintype "bidirectional"))
    )
    (net (code "21") (name "/P1.05") (class "Default")
      (node (ref "J41") (pin "2") (pinfunction "_2_2") (pintype "passive"))
      (node (ref "J7") (pin "1") (pinfunction "1_1") (pintype "passive"))
      (node (ref "U1") (pin "6") (pinfunction "P1.05/ASI(0)/RADIO(6)/AIN1_6") (pintype "bidirectional"))
    )
    (net (code "22") (name "/P1.06") (class "Default")
      (node (ref "J40") (pin "1") (pinfunction "_1_1") (pintype "passive"))
      (node (ref "J9") (pin "1") (pinfunction "1_1") (pintype "passive"))
      (node (ref "U1") (pin "7") (pinfunction "P1.06/ASO(1)/AIN2_7") (pintype "bidirectional"))
    )
    (net (code "23") (name "/P1.07") (class "Default")
      (node (ref "J11") (pin "1") (pinfunction "1_1") (pintype "passive"))
      (node (ref "J38") (pin "2") (pinfunction "_2_2") (pintype "passive"))
      (node (ref "U1") (pin "8") (pinfunction "P1.07/ASI(1)/AIN3_8") (pintype "bidirectional"))
    )
    (net (code "24") (name "/P1.08") (class "Default")
      (node (ref "J13") (pin "1") (pinfunction "1_1") (pintype "passive"))
      (node (ref "J37") (pin "2") (pinfunction "_2_2") (pintype "passive"))
      (node (ref "U1") (pin "9") (pinfunction "P1.08/CLK16M/EXTREF_9") (pintype "bidirectional"))
    )
    (net (code "25") (name "/P1.09") (class "Default")
      (node (ref "J15") (pin "1") (pinfunction "1_1") (pintype "passive"))
      (node (ref "U1") (pin "37") (pinfunction "P1.09/ASO(2)/RADIO(0)_37") (pintype "bidirectional"))
      (node (ref "U5") (pin "4") (pinfunction "VDD_4") (pintype "power_in"))
    )
    (net (code "26") (name "/P1.10") (class "Default")
      (node (ref "J20") (pin "1") (pinfunction "1_1") (pintype "passive"))
      (node (ref "U1") (pin "38") (pinfunction "P1.10/ASI(2)/RADIO(1)_38") (pintype "bidirectional"))
      (node (ref "U5") (pin "6") (pinfunction "CTRL_6") (pintype "input"))
    )
    (net (code "27") (name "/P1.11") (class "Default")
      (node (ref "J23") (pin "1") (pinfunction "1_1") (pintype "passive"))
      (node (ref "U1") (pin "39") (pinfunction "P1.11/ASO(3)/RADIO(2)/AIN4_39") (pintype "bidirectional"))
    )
    (net (code "28") (name "/P1.12") (class "Default")
      (node (ref "J26") (pin "1") (pinfunction "1_1") (pintype "passive"))
      (node (ref "U1") (pin "40") (pinfunction "P1.12/ASI(3)/RADIO(3)/AIN5_40") (pintype "bidirectional"))
    )
    (net (code "29") (name "/P1.13") (class "Default")
      (node (ref "J29") (pin "1") (pinfunction "1_1") (pintype "passive"))
      (node (ref "U1") (pin "41") (pinfunction "P1.13/RADIO(4)/AIN6_41") (pintype "bidirectional"))
    )
    (net (code "30") (name "/P1.14") (class "Default")
      (node (ref "J31") (pin "1") (pinfunction "1_1") (pintype "passive"))
      (node (ref "U1") (pin "42") (pinfunction "P1.14/RADIO(5)/AIN7_42") (pintype "bidirectional"))
    )
    (net (code "31") (name "/P2.00") (class "Default")
      (node (ref "J2") (pin "1") (pinfunction "1_1") (pintype "passive"))
      (node (ref "J43") (pin "1") (pinfunction "_1_1") (pintype "passive"))
      (node (ref "U1") (pin "11") (pinfunction "P2.00_11") (pintype "bidirectional"))
    )
    (net (code "32") (name "/P2.01") (class "Default")
      (node (ref "J4") (pin "1") (pinfunction "1_1") (pintype "passive"))
      (node (ref "J44") (pin "1") (pinfunction "_1_1") (pintype "passive"))
      (node (ref "U1") (pin "12") (pinfunction "P2.01_12") (pintype "bidirectional"))
    )
    (net (code "33") (name "/P2.02") (class "Default")
      (node (ref "J45") (pin "1") (pinfunction "_1_1") (pintype "passive"))
      (node (ref "J6") (pin "1") (pinfunction "1_1") (pintype "passive"))
      (node (ref "U1") (pin "13") (pinfunction "P2.02_13") (pintype "bidirectional"))
    )
    (net (code "34") (name "/P2.03") (class "Default")
      (node (ref "J46") (pin "1") (pinfunction "_1_1") (pintype "passive"))
      (node (ref "J8") (pin "1") (pinfunction "1_1") (pintype "passive"))
      (node (ref "U1") (pin "14") (pinfunction "P2.03_14") (pintype "bidirectional"))
    )
    (net (code "35") (name "/P2.04") (class "Default")
      (node (ref "J10") (pin "1") (pinfunction "1_1") (pintype "passive"))
      (node (ref "U1") (pin "15") (pinfunction "P2.04_15") (pintype "bidirectional"))
    )
    (net (code "36") (name "/P2.05") (class "Default")
      (node (ref "J12") (pin "1") (pinfunction "1_1") (pintype "passive"))
      (node (ref "U1") (pin "16") (pinfunction "P2.05_16") (pintype "bidirectional"))
    )
    (net (code "37") (name "/P2.06") (class "Default")
      (node (ref "J14") (pin "1") (pinfunction "1_1") (pintype "passive"))
      (node (ref "U1") (pin "17") (pinfunction "P2.06/TRACECLK_17") (pintype "bidirectional"))
    )
    (net (code "38") (name "/P2.07") (class "Default")
      (node (ref "J16") (pin "1") (pinfunction "1_1") (pintype "passive"))
      (node (ref "U1") (pin "18") (pinfunction "P2.07/TRACEDATA(0)/SWO_18") (pintype "bidirectional"))
    )
    (net (code "39") (name "/P2.08") (class "Default")
      (node (ref "J21") (pin "1") (pinfunction "1_1") (pintype "passive"))
      (node (ref "U1") (pin "19") (pinfunction "P2.08/TRACEDATA(1)_19") (pintype "bidirectional"))
    )
    (net (code "40") (name "/P2.09") (class "Default")
      (node (ref "J24") (pin "1") (pinfunction "1_1") (pintype "passive"))
      (node (ref "U1") (pin "20") (pinfunction "P2.09/TRACEDATA(2)_20") (pintype "bidirectional"))
    )
    (net (code "41") (name "/P2.10") (class "Default")
      (node (ref "J27") (pin "1") (pinfunction "1_1") (pintype "passive"))
      (node (ref "U1") (pin "21") (pinfunction "P2.10/TRACEDATA(3)_21") (pintype "bidirectional"))
    )
    (net (code "42") (name "/RF_Co-ax") (class "Default")
      (node (ref "C21") (pin "2") (pintype "passive"))
      (node (ref "J59") (pin "1") (pinfunction "SIG_1") (pintype "passive"))
      (node (ref "L7") (pin "2") (pinfunction "2_2") (pintype "passive"))
    )
    (net (code "43") (name "/RF_IFA") (class "Default")
      (node (ref "A1") (pin "1") (pinfunction "RF_IN_1") (pintype "passive"))
      (node (ref "C22") (pin "2") (pintype "passive"))
      (node (ref "L8") (pin "2") (pinfunction "2_2") (pintype "passive"))
    )
    (net (code "44") (name "/RF_OUT") (class "Default")
      (node (ref "C9") (pin "2") (pintype "passive"))
      (node (ref "L4") (pin "2") (pinfunction "2_2") (pintype "passive"))
      (node (ref "U5") (pin "5") (pinfunction "RFIN_5") (pintype "input"))
    )
    (net (code "45") (name "/RST") (class "Default")
      (node (ref "J51") (pin "1") (pinfunction "1_1") (pintype "passive"))
      (node (ref "R9") (pin "2") (pintype "passive"))
    )
    (net (code "46") (name "/TDI") (class "Default")
      (node (ref "J47") (pin "1") (pinfunction "1_1") (pintype "passive"))
      (node (ref "R4") (pin "2") (pintype "passive"))
    )
    (net (code "47") (name "/TDO") (class "Default")
      (node (ref "J49") (pin "1") (pinfunction "1_1") (pintype "passive"))
      (node (ref "R5") (pin "2") (pintype "passive"))
    )
    (net (code "48") (name "/UART_RX") (class "Default")
      (node (ref "J22") (pin "1") (pinfunction "1_1") (pintype "passive"))
      (node (ref "J58") (pin "1") (pinfunction "_1_1") (pintype "passive"))
      (node (ref "U1") (pin "24") (pinfunction "P0.01_24") (pintype "bidirectional"))
    )
    (net (code "49") (name "/UART_TX") (class "Default")
      (node (ref "J17") (pin "1") (pinfunction "1_1") (pintype "passive"))
      (node (ref "J57") (pin "1") (pinfunction "_1_1") (pintype "passive"))
      (node (ref "U1") (pin "23") (pinfunction "P0.00_23") (pintype "bidirectional"))
    )
    (net (code "50") (name "/VDD_A") (class "Default")
      (node (ref "C19") (pin "2") (pintype "passive"))
      (node (ref "L6") (pin "1") (pinfunction "1_1") (pintype "passive"))
      (node (ref "U4") (pin "8") (pinfunction "VDD_8") (pintype "passive"))
    )
    (net (code "51") (name "/XC1") (class "Default")
      (node (ref "U1") (pin "34") (pinfunction "XC1_34") (pintype "input"))
      (node (ref "Y1") (pin "3") (pinfunction "3_3") (pintype "passive"))
    )
    (net (code "52") (name "/XC2") (class "Default")
      (node (ref "U1") (pin "35") (pinfunction "XC2_35") (pintype "input"))
      (node (ref "Y1") (pin "1") (pinfunction "1_1") (pintype "passive"))
    )
    (net (code "53") (name "3V") (class "Default")
      (node (ref "BT1") (pin "2") (pinfunction "A_2") (pintype "passive"))
      (node (ref "SW1") (pin "1") (pinfunction "1_1") (pintype "passive"))
    )
    (net (code "54") (name "GND") (class "Default")
      (node (ref "A1") (pin "2") (pinfunction "GND_2") (pintype "passive"))
      (node (ref "BT1") (pin "1") (pinfunction "C_1") (pintype "passive"))
      (node (ref "C1") (pin "1") (pintype "passive"))
      (node (ref "C10") (pin "1") (pintype "passive"))
      (node (ref "C11") (pin "1") (pintype "passive"))
      (node (ref "C12") (pin "1") (pintype "passive"))
      (node (ref "C13") (pin "1") (pintype "passive"))
      (node (ref "C14") (pin "1") (pintype "passive"))
      (node (ref "C15") (pin "1") (pintype "passive"))
      (node (ref "C16") (pin "1") (pintype "passive"))
      (node (ref "C17") (pin "1") (pintype "passive"))
      (node (ref "C18") (pin "1") (pintype "passive"))
      (node (ref "C19") (pin "1") (pintype "passive"))
      (node (ref "C2") (pin "1") (pintype "passive"))
      (node (ref "C20") (pin "1") (pintype "passive"))
      (node (ref "C21") (pin "1") (pintype "passive"))
      (node (ref "C22") (pin "1") (pintype "passive"))
      (node (ref "C3") (pin "1") (pintype "passive"))
      (node (ref "C4") (pin "1") (pintype "passive"))
      (node (ref "C5") (pin "1") (pintype "passive"))
      (node (ref "C6") (pin "1") (pintype "passive"))
      (node (ref "C7") (pin "1") (pintype "passive"))
      (node (ref "C8") (pin "1") (pintype "passive"))
      (node (ref "C9") (pin "1") (pintype "passive"))
      (node (ref "D1") (pin "2") (pinfunction "GND_2") (pintype "power_in"))
      (node (ref "DS3") (pin "2") (pinfunction "K_2") (pintype "passive"))
      (node (ref "J18") (pin "1") (pinfunction "1_1") (pintype "passive"))
      (node (ref "J19") (pin "1") (pinfunction "1_1") (pintype "passive"))
      (node (ref "J1_USB") (pin "1") (pinfunction "MNT_1_1") (pintype "passive"))
      (node (ref "J1_USB") (pin "2") (pinfunction "MNT_2_2") (pintype "passive"))
      (node (ref "J1_USB") (pin "3") (pinfunction "MNT_3_3") (pintype "passive"))
      (node (ref "J1_USB") (pin "4") (pinfunction "MNT_4_4") (pintype "passive"))
      (node (ref "J1_USB") (pin "A1-B12") (pinfunction "GND_A1-B12") (pintype "passive"))
      (node (ref "J1_USB") (pin "B1-A12") (pinfunction "GND_B1-A12") (pintype "passive"))
      (node (ref "J35") (pin "1") (pinfunction "1_1") (pintype "passive"))
      (node (ref "J36") (pin "1") (pinfunction "1_1") (pintype "passive"))
      (node (ref "J50") (pin "1") (pinfunction "1_1") (pintype "passive"))
      (node (ref "J59") (pin "2") (pinfunction "GND_2") (pintype "power_in"))
      (node (ref "J59") (pin "3") (pinfunction "GND_3") (pintype "power_in"))
      (node (ref "R2") (pin "1") (pintype "passive"))
      (node (ref "R3") (pin "1") (pintype "passive"))
      (node (ref "R7") (pin "1") (pintype "passive"))
      (node (ref "SW1") (pin "4") (pinfunction "MNT_1_4") (pintype "passive"))
      (node (ref "SW1") (pin "5") (pinfunction "MNT_2_5") (pintype "passive"))
      (node (ref "SW3") (pin "3") (pinfunction "2_3") (pintype "passive"))
      (node (ref "SW3") (pin "4") (pinfunction "2_4") (pintype "passive"))
      (node (ref "SW4") (pin "3") (pinfunction "2_3") (pintype "passive"))
      (node (ref "SW4") (pin "4") (pinfunction "2_4") (pintype "passive"))
      (node (ref "U1") (pin "32") (pinfunction "VSS_PA_32") (pintype "power_in"))
      (node (ref "U1") (pin "44") (pinfunction "VSS_44") (pintype "power_in"))
      (node (ref "U1") (pin "49") (pinfunction "VSS_49") (pintype "power_in"))
      (node (ref "U2") (pin "2") (pinfunction "GND_2") (pintype "power_in"))
      (node (ref "U3") (pin "17") (pinfunction "VSS_EP_17") (pintype "power_in"))
      (node (ref "U4") (pin "6") (pinfunction "GNDIO_6") (pintype "passive"))
      (node (ref "U4") (pin "7") (pinfunction "GND_7") (pintype "passive"))
      (node (ref "U5") (pin "2") (pinfunction "GND_2") (pintype "power_in"))
      (node (ref "Y1") (pin "2") (pinfunction "2_2") (pintype "passive"))
      (node (ref "Y1") (pin "4") (pinfunction "4_4") (pintype "passive"))
    )
    (net (code "55") (name "Net-(C7-Pad2)") (class "Default")
      (node (ref "C7") (pin "2") (pintype "passive"))
      (node (ref "L2") (pin "2") (pinfunction "2_2") (pintype "passive"))
      (node (ref "L3") (pin "1") (pinfunction "1_1") (pintype "passive"))
    )
    (net (code "56") (name "Net-(C8-Pad2)") (class "Default")
      (node (ref "C8") (pin "2") (pintype "passive"))
      (node (ref "L3") (pin "2") (pinfunction "2_2") (pintype "passive"))
      (node (ref "L4") (pin "1") (pinfunction "1_1") (pintype "passive"))
    )
    (net (code "57") (name "Net-(D1-DATA_IN)") (class "Default")
      (node (ref "D1") (pin "3") (pinfunction "DATA_IN_3") (pintype "input"))
      (node (ref "R16") (pin "2") (pintype "passive"))
    )
    (net (code "58") (name "Net-(DS1-K)") (class "Default")
      (node (ref "DS1") (pin "2") (pinfunction "K_2") (pintype "passive"))
      (node (ref "R2") (pin "2") (pintype "passive"))
    )
    (net (code "59") (name "Net-(DS2-K)") (class "Default")
      (node (ref "DS2") (pin "2") (pinfunction "K_2") (pintype "passive"))
      (node (ref "R12") (pin "2") (pintype "passive"))
    )
    (net (code "60") (name "Net-(DS3-A)") (class "Default")
      (node (ref "DS3") (pin "1") (pinfunction "A_1") (pintype "passive"))
      (node (ref "R17") (pin "1") (pintype "passive"))
    )
    (net (code "61") (name "Net-(J1_USB-CC1)") (class "Default")
      (node (ref "J1_USB") (pin "A5") (pinfunction "CC1_A5") (pintype "passive"))
      (node (ref "R3") (pin "2") (pintype "passive"))
    )
    (net (code "62") (name "Net-(J1_USB-CC2)") (class "Default")
      (node (ref "J1_USB") (pin "B5") (pinfunction "CC2_B5") (pintype "passive"))
      (node (ref "R7") (pin "2") (pintype "passive"))
    )
    (net (code "63") (name "Net-(J40-_2)") (class "Default")
      (node (ref "J40") (pin "2") (pinfunction "_2_2") (pintype "passive"))
      (node (ref "U4") (pin "1") (pinfunction "SDO_1") (pintype "passive"))
    )
    (net (code "64") (name "Net-(J41-_1)") (class "Default")
      (node (ref "J41") (pin "1") (pinfunction "_1_1") (pintype "passive"))
      (node (ref "U4") (pin "9") (pinfunction "INT2_9") (pintype "passive"))
    )
    (net (code "65") (name "Net-(J42-_2)") (class "Default")
      (node (ref "J42") (pin "2") (pinfunction "_2_2") (pintype "passive"))
      (node (ref "U4") (pin "4") (pinfunction "INT1_4") (pintype "passive"))
    )
    (net (code "66") (name "Net-(J43-_2)") (class "Default")
      (node (ref "J43") (pin "2") (pinfunction "_2_2") (pintype "passive"))
      (node (ref "R17") (pin "2") (pintype "passive"))
    )
    (net (code "67") (name "Net-(J44-_2)") (class "Default")
      (node (ref "J44") (pin "2") (pinfunction "_2_2") (pintype "passive"))
      (node (ref "R16") (pin "1") (pintype "passive"))
    )
    (net (code "68") (name "Net-(J45-_2)") (class "Default")
      (node (ref "J45") (pin "2") (pinfunction "_2_2") (pintype "passive"))
      (node (ref "R18") (pin "2") (pintype "passive"))
    )
    (net (code "69") (name "Net-(J46-_2)") (class "Default")
      (node (ref "J46") (pin "2") (pinfunction "_2_2") (pintype "passive"))
      (node (ref "R19") (pin "2") (pintype "passive"))
    )
    (net (code "70") (name "Net-(J48-Pad1)") (class "Default")
      (node (ref "J48") (pin "1") (pinfunction "1_1") (pintype "passive"))
      (node (ref "J55") (pin "1") (pinfunction "1_1") (pintype "passive"))
    )
    (net (code "71") (name "Net-(J52-Pad1)") (class "Default")
      (node (ref "J52") (pin "1") (pinfunction "1_1") (pintype "passive"))
      (node (ref "J56") (pin "1") (pinfunction "1_1") (pintype "passive"))
    )
    (net (code "72") (name "Net-(J53-_1)") (class "Default")
      (node (ref "J53") (pin "1") (pinfunction "_1_1") (pintype "passive"))
      (node (ref "U1") (pin "26") (pinfunction "SWDCLK_26") (pintype "input"))
    )
    (net (code "73") (name "Net-(J54-_1)") (class "Default")
      (node (ref "J54") (pin "1") (pinfunction "_1_1") (pintype "passive"))
      (node (ref "U1") (pin "25") (pinfunction "SWDIO_25") (pintype "bidirectional"))
    )
    (net (code "74") (name "Net-(J57-_2)") (class "Default")
      (node (ref "J57") (pin "2") (pinfunction "_2_2") (pintype "passive"))
      (node (ref "R10") (pin "2") (pintype "passive"))
    )
    (net (code "75") (name "Net-(J58-_2)") (class "Default")
      (node (ref "J58") (pin "2") (pinfunction "_2_2") (pintype "passive"))
      (node (ref "R11") (pin "1") (pintype "passive"))
    )
    (net (code "76") (name "Net-(R15-Pad2)") (class "Default")
      (node (ref "R15") (pin "2") (pintype "passive"))
      (node (ref "SW2") (pin "1") (pinfunction "1_1") (pintype "passive"))
      (node (ref "SW2") (pin "2") (pinfunction "1_2") (pintype "passive"))
    )
    (net (code "77") (name "Net-(R18-Pad1)") (class "Default")
      (node (ref "R18") (pin "1") (pintype "passive"))
      (node (ref "SW3") (pin "1") (pinfunction "1_1") (pintype "passive"))
      (node (ref "SW3") (pin "2") (pinfunction "1_2") (pintype "passive"))
    )
    (net (code "78") (name "Net-(R19-Pad1)") (class "Default")
      (node (ref "R19") (pin "1") (pintype "passive"))
      (node (ref "SW4") (pin "1") (pinfunction "1_1") (pintype "passive"))
      (node (ref "SW4") (pin "2") (pinfunction "1_2") (pintype "passive"))
    )
    (net (code "79") (name "Net-(U1A-~{RESET})") (class "Default")
      (node (ref "C13") (pin "2") (pintype "passive"))
      (node (ref "U1") (pin "30") (pinfunction "~{RESET}_30") (pintype "input"))
    )
    (net (code "80") (name "Net-(U1C-P1.00{slash}XL1)") (class "Default")
      (node (ref "U1") (pin "1") (pinfunction "P1.00/XL1_1") (pintype "bidirectional"))
      (node (ref "Y2") (pin "2") (pinfunction "2_2") (pintype "passive"))
    )
    (net (code "81") (name "Net-(U1C-P1.01{slash}XL2)") (class "Default")
      (node (ref "U1") (pin "2") (pinfunction "P1.01/XL2_2") (pintype "bidirectional"))
      (node (ref "Y2") (pin "1") (pinfunction "1_1") (pintype "passive"))
    )
    (net (code "82") (name "Net-(U3-P1.1{slash}T2EX{slash}CAP2{slash}TIN1{slash}AIN0)") (class "Default")
      (node (ref "R12") (pin "1") (pintype "passive"))
      (node (ref "U3") (pin "11") (pinfunction "P1.1/T2EX/CAP2/TIN1/AIN0_11") (pintype "bidirectional"))
    )
    (net (code "83") (name "Net-(U3-P1.4{slash}T2_{slash}CAP1_{slash}SCS{slash}TIN2{slash}AIN1)") (class "Default")
      (node (ref "R5") (pin "1") (pintype "passive"))
      (node (ref "U3") (pin "3") (pinfunction "P1.4/T2_/CAP1_/SCS/TIN2/AIN1_3") (pintype "bidirectional"))
    )
    (net (code "84") (name "Net-(U3-P1.5{slash}MOSI{slash}PWM1{slash}TIN3{slash}AIN2)") (class "Default")
      (node (ref "R6") (pin "1") (pintype "passive"))
      (node (ref "U3") (pin "2") (pinfunction "P1.5/MOSI/PWM1/TIN3/AIN2_2") (pintype "bidirectional"))
    )
    (net (code "85") (name "Net-(U3-P1.6{slash}MISO{slash}RXD1{slash}TIN4)") (class "Default")
      (node (ref "R8") (pin "1") (pintype "passive"))
      (node (ref "U3") (pin "5") (pinfunction "P1.6/MISO/RXD1/TIN4_5") (pintype "bidirectional"))
    )
    (net (code "86") (name "Net-(U3-P1.7{slash}SCK{slash}TXD1{slash}TIN5)") (class "Default")
      (node (ref "R9") (pin "1") (pintype "passive"))
      (node (ref "U3") (pin "6") (pinfunction "P1.7/SCK/TXD1/TIN5_6") (pintype "bidirectional"))
    )
    (net (code "87") (name "Net-(U3-P3.2{slash}TXD1_{slash}INT0{slash}VBUS1{slash}AIN3)") (class "Default")
      (node (ref "R4") (pin "1") (pintype "passive"))
      (node (ref "U3") (pin "4") (pinfunction "P3.2/TXD1_/INT0/VBUS1/AIN3_4") (pintype "bidirectional"))
    )
    (net (code "88") (name "Net-(U3-RST{slash}T2EX_{slash}CAP2_)") (class "Default")
      (node (ref "C17") (pin "2") (pintype "passive"))
      (node (ref "U3") (pin "7") (pinfunction "RST/T2EX_/CAP2__7") (pintype "input"))
    )
    (net (code "89") (name "Net-(U5-RF1)") (class "Default")
      (node (ref "L7") (pin "1") (pinfunction "1_1") (pintype "passive"))
      (node (ref "U5") (pin "3") (pinfunction "RF1_3") (pintype "passive"))
    )
    (net (code "90") (name "Net-(U5-RF2)") (class "Default")
      (node (ref "L8") (pin "1") (pinfunction "1_1") (pintype "passive"))
      (node (ref "U5") (pin "1") (pinfunction "RF2_1") (pintype "passive"))
    )
    (net (code "91") (name "VCC_nRF") (class "Default")
      (node (ref "C1") (pin "2") (pintype "passive"))
      (node (ref "C18") (pin "2") (pintype "passive"))
      (node (ref "C2") (pin "2") (pintype "passive"))
      (node (ref "C3") (pin "2") (pintype "passive"))
      (node (ref "C4") (pin "2") (pintype "passive"))
      (node (ref "C5") (pin "2") (pintype "passive"))
      (node (ref "J32") (pin "1") (pinfunction "1_1") (pintype "passive"))
      (node (ref "J34") (pin "1") (pinfunction "1_1") (pintype "passive"))
      (node (ref "L6") (pin "2") (pinfunction "2_2") (pintype "passive"))
      (node (ref "R13") (pin "2") (pintype "passive"))
      (node (ref "R14") (pin "2") (pintype "passive"))
      (node (ref "SW1") (pin "3") (pinfunction "C_3") (pintype "passive"))
      (node (ref "U1") (pin "10") (pinfunction "VDD_10") (pintype "power_in"))
      (node (ref "U1") (pin "22") (pinfunction "VDD_22") (pintype "power_in"))
      (node (ref "U1") (pin "36") (pinfunction "VDD_36") (pintype "power_in"))
      (node (ref "U1") (pin "47") (pinfunction "VDD_47") (pintype "power_in"))
      (node (ref "U1") (pin "48") (pinfunction "VDD_48") (pintype "power_in"))
      (node (ref "U4") (pin "5") (pinfunction "VDDIO_5") (pintype "passive"))
    )
    (net (code "92") (name "VDD_3V3") (class "Default")
      (node (ref "C14") (pin "2") (pintype "passive"))
      (node (ref "C16") (pin "2") (pintype "passive"))
      (node (ref "DS1") (pin "1") (pinfunction "A_1") (pintype "passive"))
      (node (ref "DS2") (pin "1") (pinfunction "A_1") (pintype "passive"))
      (node (ref "J33") (pin "1") (pinfunction "1_1") (pintype "passive"))
      (node (ref "SW1") (pin "2") (pinfunction "2_2") (pintype "passive"))
      (node (ref "SW2") (pin "3") (pinfunction "2_3") (pintype "passive"))
      (node (ref "SW2") (pin "4") (pinfunction "2_4") (pintype "passive"))
      (node (ref "U2") (pin "5") (pinfunction "VOUT_5") (pintype "power_in"))
      (node (ref "U3") (pin "1") (pinfunction "V33_1") (pintype "power_in"))
      (node (ref "U3") (pin "16") (pinfunction "VCC/VDD_16") (pintype "power_in"))
    )
    (net (code "93") (name "unconnected-(D1-DATA_OUT-Pad1)") (class "Default")
      (node (ref "D1") (pin "1") (pinfunction "DATA_OUT_1") (pintype "output+no_connect"))
    )
    (net (code "94") (name "unconnected-(J1_USB-SBU1-PadA8)") (class "Default")
      (node (ref "J1_USB") (pin "A8") (pinfunction "SBU1_A8") (pintype "passive+no_connect"))
    )
    (net (code "95") (name "unconnected-(J1_USB-SBU2-PadB8)") (class "Default")
      (node (ref "J1_USB") (pin "B8") (pinfunction "SBU2_B8") (pintype "passive+no_connect"))
    )
    (net (code "96") (name "unconnected-(U2-NC-Pad4)") (class "Default")
      (node (ref "U2") (pin "4") (pinfunction "NC_4") (pintype "power_in+no_connect"))
    )
    (net (code "97") (name "unconnected-(U3-P1.0{slash}T2{slash}CAP1{slash}TIN0-Pad8)") (class "Default")
      (node (ref "U3") (pin "8") (pinfunction "P1.0/T2/CAP1/TIN0_8") (pintype "bidirectional+no_connect"))
    )
    (net (code "98") (name "unconnected-(U3-P3.3{slash}INT1-Pad12)") (class "Default")
      (node (ref "U3") (pin "12") (pinfunction "P3.3/INT1_12") (pintype "bidirectional+no_connect"))
    )
    (net (code "99") (name "unconnected-(U3-P3.4{slash}PWM2{slash}RXD1_{slash}T0-Pad13)") (class "Default")
      (node (ref "U3") (pin "13") (pinfunction "P3.4/PWM2/RXD1_/T0_13") (pintype "bidirectional+no_connect"))
    )
    (net (code "100") (name "unconnected-(U4-ASCx-Pad3)") (class "Default")
      (node (ref "U4") (pin "3") (pinfunction "ASCx_3") (pintype "passive+no_connect"))
    )
    (net (code "101") (name "unconnected-(U4-ASDx-Pad2)") (class "Default")
      (node (ref "U4") (pin "2") (pinfunction "ASDx_2") (pintype "passive+no_connect"))
    )
    (net (code "102") (name "unconnected-(U4-OSCB-Pad10)") (class "Default")
      (node (ref "U4") (pin "10") (pinfunction "OSCB_10") (pintype "passive+no_connect"))
    )
    (net (code "103") (name "unconnected-(U4-OSDO-Pad11)") (class "Default")
      (node (ref "U4") (pin "11") (pinfunction "OSDO_11") (pintype "passive+no_connect"))
    )
  )
)
